# knowles_bkout.net
KiCad netlist of a schematic drawn in EAGLE
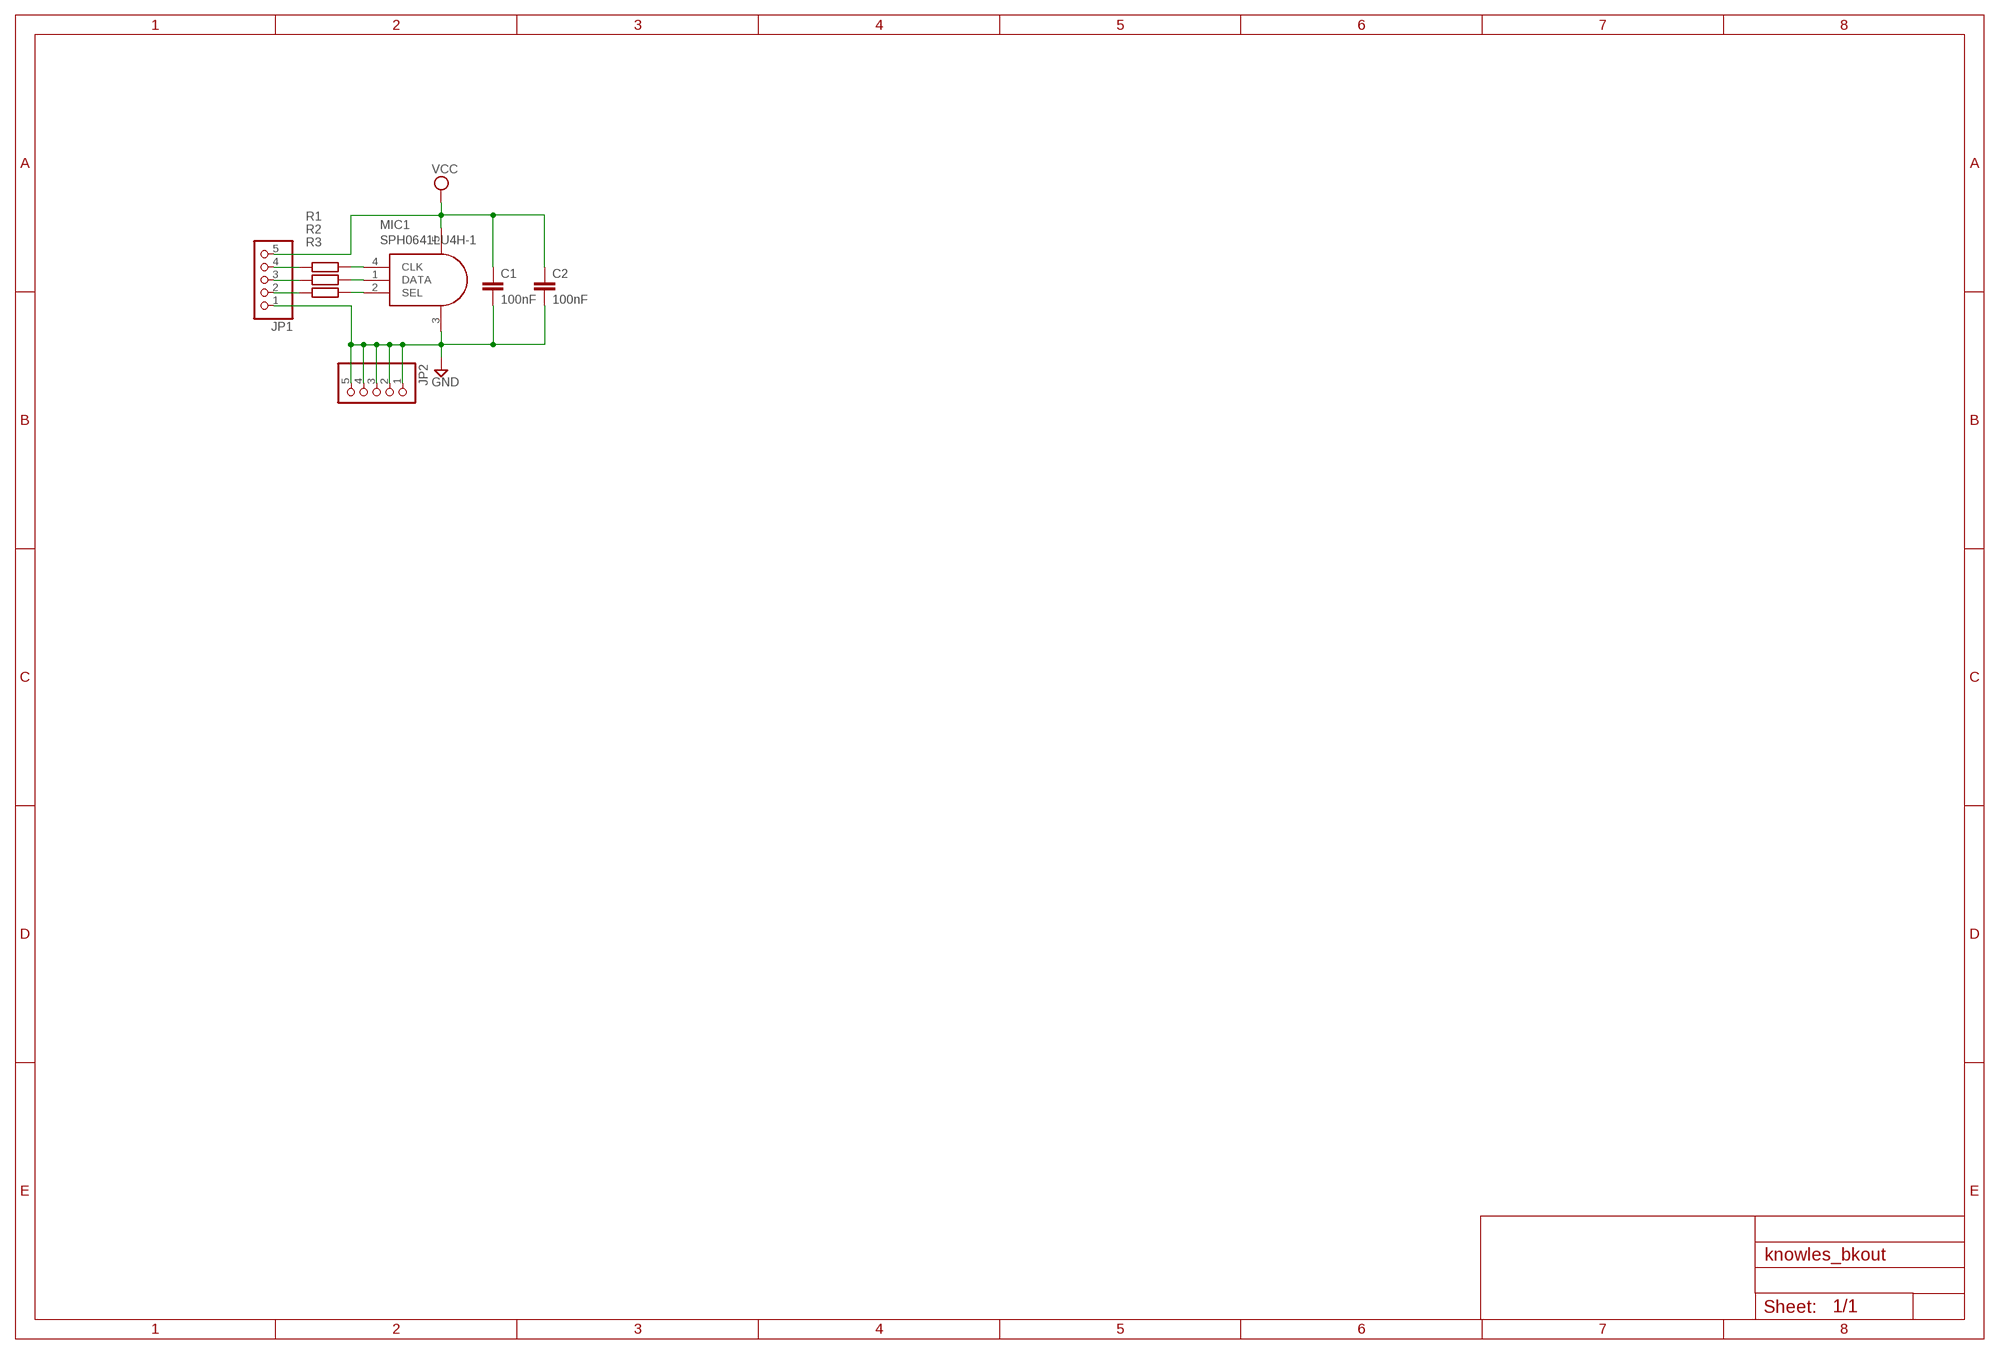
[diagram p0: schematic, sheet 1]

(export (version "E")
  (design (tool "Eeschema 10.0.6"))
  (components
    (comp (ref "C1")
      (value "100nF")
      (footprint "eagle-import:C0805K")
      (libsource (lib "eagle-import") (part "C-EUC0805K"))
    )
    (comp (ref "C2")
      (value "100nF")
      (footprint "eagle-import:C0805K")
      (libsource (lib "eagle-import") (part "C-EUC0805K"))
    )
    (comp (ref "JP1")
      (value "PINHD-1X5")
      (footprint "eagle-import:1X05")
      (libsource (lib "eagle-import") (part "PINHD-1X5"))
    )
    (comp (ref "JP2")
      (value "PINHD-1X5")
      (footprint "eagle-import:1X05")
      (libsource (lib "eagle-import") (part "PINHD-1X5"))
    )
    (comp (ref "MIC1")
      (value "SPH0641LU4H-1")
      (footprint "eagle-import:SPH0641LU4H-1")
      (libsource (lib "eagle-import") (part "SPH0641LU4H-1"))
    )
    (comp (ref "R1")
      (value "R-EU_R0603")
      (footprint "eagle-import:R0603")
      (libsource (lib "eagle-import") (part "R-EU_R0603"))
    )
    (comp (ref "R2")
      (value "R-EU_R0603")
      (footprint "eagle-import:R0603")
      (libsource (lib "eagle-import") (part "R-EU_R0603"))
    )
    (comp (ref "R3")
      (value "R-EU_R0603")
      (footprint "eagle-import:R0603")
      (libsource (lib "eagle-import") (part "R-EU_R0603"))
    )
  )
  (nets
    (net (code "1") (name "GND") (class "Default")
      (node (ref "C1") (pin "2") (pinfunction "2_2") (pintype "passive"))
      (node (ref "C2") (pin "2") (pinfunction "2_2") (pintype "passive"))
      (node (ref "JP1") (pin "1") (pinfunction "1_1") (pintype "passive"))
      (node (ref "JP2") (pin "1") (pinfunction "1_1") (pintype "passive"))
      (node (ref "JP2") (pin "2") (pinfunction "2_2") (pintype "passive"))
      (node (ref "JP2") (pin "3") (pinfunction "3_3") (pintype "passive"))
      (node (ref "JP2") (pin "4") (pinfunction "4_4") (pintype "passive"))
      (node (ref "JP2") (pin "5") (pinfunction "5_5") (pintype "passive"))
      (node (ref "MIC1") (pin "3") (pinfunction "GND_3") (pintype "bidirectional"))
    )
    (net (code "2") (name "Net-(JP1-Pad2)") (class "Default")
      (node (ref "JP1") (pin "2") (pinfunction "2_2") (pintype "passive"))
      (node (ref "R3") (pin "1") (pinfunction "1_1") (pintype "passive"))
    )
    (net (code "3") (name "Net-(JP1-Pad3)") (class "Default")
      (node (ref "JP1") (pin "3") (pinfunction "3_3") (pintype "passive"))
      (node (ref "R2") (pin "1") (pinfunction "1_1") (pintype "passive"))
    )
    (net (code "4") (name "Net-(JP1-Pad4)") (class "Default")
      (node (ref "JP1") (pin "4") (pinfunction "4_4") (pintype "passive"))
      (node (ref "R1") (pin "1") (pinfunction "1_1") (pintype "passive"))
    )
    (net (code "5") (name "Net-(MIC1-CLK)") (class "Default")
      (node (ref "MIC1") (pin "4") (pinfunction "CLK_4") (pintype "bidirectional"))
      (node (ref "R1") (pin "2") (pinfunction "2_2") (pintype "passive"))
    )
    (net (code "6") (name "Net-(MIC1-DATA)") (class "Default")
      (node (ref "MIC1") (pin "1") (pinfunction "DATA_1") (pintype "bidirectional"))
      (node (ref "R2") (pin "2") (pinfunction "2_2") (pintype "passive"))
    )
    (net (code "7") (name "Net-(MIC1-SEL)") (class "Default")
      (node (ref "MIC1") (pin "2") (pinfunction "SEL_2") (pintype "bidirectional"))
      (node (ref "R3") (pin "2") (pinfunction "2_2") (pintype "passive"))
    )
    (net (code "8") (name "VCC") (class "Default")
      (node (ref "C1") (pin "1") (pinfunction "1_1") (pintype "passive"))
      (node (ref "C2") (pin "1") (pinfunction "1_1") (pintype "passive"))
      (node (ref "JP1") (pin "5") (pinfunction "5_5") (pintype "passive"))
      (node (ref "MIC1") (pin "5") (pinfunction "VDD_5") (pintype "bidirectional"))
    )
  )
)
